# 04-Power-V3P3.net
KiCad netlist of a schematic drawn in Altium Designer
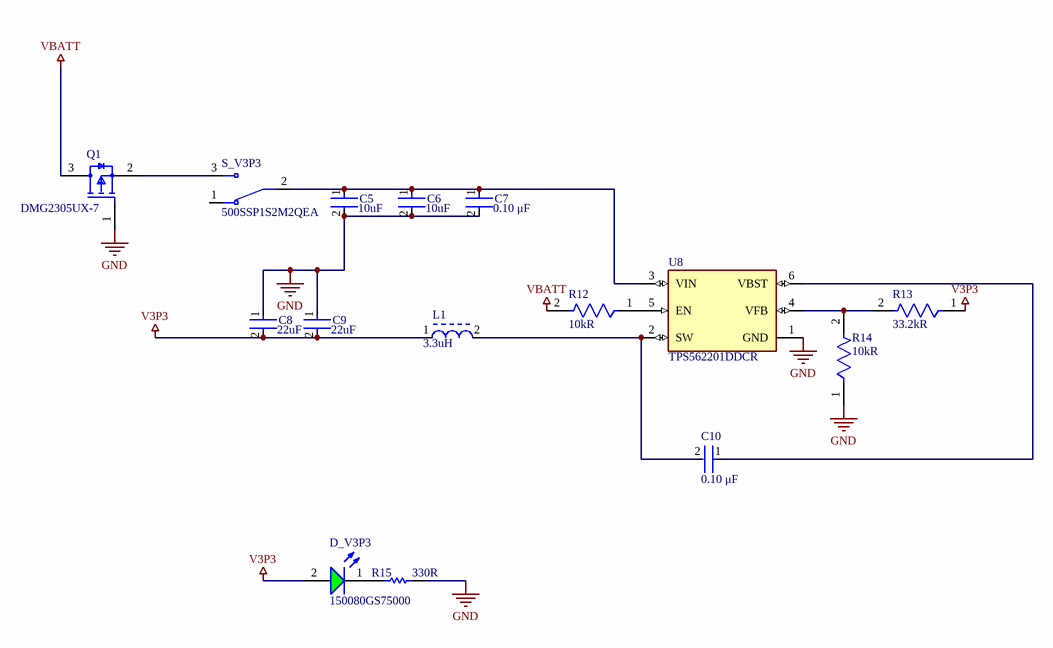
[diagram p0: 04-Power-V3P3.SchDoc]

(export (version "E")
  (design (tool "Eeschema 10.0.6"))
  (components
    (comp (ref "C5")
      (value "GRM21BR61E106KA73L")
      (footprint "FP-GRM21B-0_15-IPC_C")
      (description "Chip Multilayer Ceramic Capacitors for General Purpose, 0805, 10uF, X5R, 15%, 10%, 25V")
      (fields
        (field (name "VOLTAGE") "25V")
        (field (name "CAPACITANCE") "10uF")
        (field (name "TOLERANCE") "10%")
      )
      (libsource (lib "Altium Content Vault") (part "b4654b650e69147ec39a6b967a45e02"))
    )
    (comp (ref "C6")
      (value "GRM21BR61E106KA73L")
      (footprint "FP-GRM21B-0_15-IPC_C")
      (description "Chip Multilayer Ceramic Capacitors for General Purpose, 0805, 10uF, X5R, 15%, 10%, 25V")
      (fields
        (field (name "VOLTAGE") "25V")
        (field (name "CAPACITANCE") "10uF")
        (field (name "TOLERANCE") "10%")
      )
      (libsource (lib "Altium Content Vault") (part "b4654b650e69147ec39a6b967a45e02"))
    )
    (comp (ref "C7")
      (value "0.10 μF")
      (footprint "FP-C0805C-DN-MFG")
      (description "CAP CER 0.1UF 50V X7R 0805")
      (fields
        (field (name "MANUFACTURER PART NUMBER") "C0805C104K5RACTU")
        (field (name "MANUFACTURER") "KEMET")
      )
      (libsource (lib "Altium Content Vault") (part "b4654b650e69147ec39a6b967a45e02"))
    )
    (comp (ref "C8")
      (value "GRM21BR61E226ME44L")
      (footprint "FP-GRM21B-0_2-e0_2_0_7-IPC_B")
      (description "Chip Multilayer Ceramic Capacitors for General Purpose, 0805, 22uF, X5R, 15%, 20%, 25V")
      (fields
        (field (name "TOLERANCE") "20%")
        (field (name "CAPACITANCE") "22uF")
        (field (name "VOLTAGE") "25V")
      )
      (libsource (lib "Altium Content Vault") (part "b4654b650e69147ec39a6b967a45e02"))
    )
    (comp (ref "C9")
      (value "GRM21BR61E226ME44L")
      (footprint "FP-GRM21B-0_2-e0_2_0_7-IPC_B")
      (description "Chip Multilayer Ceramic Capacitors for General Purpose, 0805, 22uF, X5R, 15%, 20%, 25V")
      (fields
        (field (name "TOLERANCE") "20%")
        (field (name "CAPACITANCE") "22uF")
        (field (name "VOLTAGE") "25V")
      )
      (libsource (lib "Altium Content Vault") (part "b4654b650e69147ec39a6b967a45e02"))
    )
    (comp (ref "C10")
      (value "0.10 μF")
      (footprint "FP-C0805C-DN-MFG")
      (description "CAP CER 0.1UF 50V X7R 0805")
      (fields
        (field (name "MANUFACTURER PART NUMBER") "C0805C104K5RACTU")
        (field (name "MANUFACTURER") "KEMET")
      )
      (libsource (lib "Altium Content Vault") (part "b4654b650e69147ec39a6b967a45e02"))
    )
    (comp (ref "D_V3P3")
      (value "150080GS75000")
      (footprint "WL-SMCW_0805_150080xx75000")
      (description "LED GREEN CLEAR 0805 SMD")
      (fields (field (name "MANUFACTURER") "Wurth Electronics"))
      (libsource (lib "Altium Content Vault") (part "LED_Green_2A-1K"))
    )
    (comp (ref "L1")
      (value "SRN6045-3R3Y")
      (footprint "FP-SRN6045-MFG")
      (description "FIXED IND 3.3UH 3.2A 30.2MOHM SM")
      (fields
        (field (name "INDUCTANCE") "3.3uH")
        (field (name "TOLERANCE") "30%")
        (field (name "MANUFACTURER") "Bourns")
      )
      (libsource (lib "Altium Content Vault") (part "e3fba2ffd49a0ea5f20e61e1dfb215d"))
    )
    (comp (ref "Q1")
      (value "DMG2305UX-7")
      (footprint "FP-SOT23-IPC_B")
      (description "MOSFET P-CH 20V 4.2A SOT23")
      (libsource (lib "Altium Content Vault") (part "87831b450059b469d4a68f5364f4496"))
    )
    (comp (ref "R12")
      (value "RMCF0805FT10K0")
      (footprint "FP-RMCF0805-MFG")
      (description "RES 10K OHM 1% 1/8W 0805")
      (fields
        (field (name "TOLERANCE") "1%")
        (field (name "RESISTANCE") "10kR")
        (field (name "MANUFACTURER") "Stackpole Electronics")
      )
      (libsource (lib "Altium Content Vault") (part "1029c3af85768c4190bb7ad29bc67b5"))
    )
    (comp (ref "R13")
      (value "RMCF0805FT33K2")
      (footprint "FP-RMCF0805-IPC_A")
      (description "33.2kΩ ±1% 0.125W 0805 Thick Film Chip Resistor AEC-Q200 compliant")
      (fields
        (field (name "RESISTANCE") "33.2kR")
        (field (name "TOLERANCE") "1%")
        (field (name "MANUFACTURER") "Stackpole Electronics")
      )
      (libsource (lib "Altium Content Vault") (part "1029c3af85768c4190bb7ad29bc67b5"))
    )
    (comp (ref "R14")
      (value "RMCF0805FT10K0")
      (footprint "FP-RMCF0805-MFG")
      (description "RES 10K OHM 1% 1/8W 0805")
      (fields
        (field (name "TOLERANCE") "1%")
        (field (name "RESISTANCE") "10kR")
        (field (name "MANUFACTURER") "Stackpole Electronics")
      )
      (libsource (lib "Altium Content Vault") (part "1029c3af85768c4190bb7ad29bc67b5"))
    )
    (comp (ref "R15")
      (value "330R")
      (footprint "RESC2013X60X40LL20T25")
      (description "RES SMD 330 OHM 1% 1/8W 0805")
      (fields
        (field (name "MANUFACTURER") "Panasonic")
        (field (name "MANUFACTURER PART NUMBER") "ERJ-6ENF3300V")
      )
      (libsource (lib "Altium Content Vault") (part "RES"))
    )
    (comp (ref "S_V3P3")
      (value "500SSP1S2M2QEA")
      (footprint "mjindal2_pcblib:SW_500SSP1S2M2QEA")
      (description "Slide Switch SPDT Through Hole")
      (libsource (lib "mjindal2_schlib") (part "500SSP1S2M2QEA"))
    )
    (comp (ref "U8")
      (value "TPS562201DDCR")
      (footprint "FP-DDC0006A-IPC_C")
      (description "IC REG BUCK ADJ 2A TSOT23-6")
      (libsource (lib "Altium Content Vault") (part "957e164956730ea4bf6293280af19fc"))
    )
  )
  (nets
    (net (code "1") (name "GND") (class "Default")
      (node (ref "C5") (pin "2") (pinfunction "2_2") (pintype "passive"))
      (node (ref "C6") (pin "2") (pinfunction "2_2") (pintype "passive"))
      (node (ref "C7") (pin "2") (pinfunction "2_2") (pintype "passive"))
      (node (ref "C8") (pin "1") (pinfunction "1_1") (pintype "passive"))
      (node (ref "C9") (pin "1") (pinfunction "1_1") (pintype "passive"))
      (node (ref "Q1") (pin "1") (pinfunction "GATE_1") (pintype "passive"))
      (node (ref "R14") (pin "1") (pinfunction "1_1") (pintype "passive"))
      (node (ref "R15") (pin "1") (pinfunction "1_1") (pintype "passive"))
      (node (ref "U8") (pin "1") (pinfunction "GND_1") (pintype "power_in"))
    )
    (net (code "2") (name "Net-(D_V3P3-K)") (class "Default")
      (node (ref "D_V3P3") (pin "1") (pinfunction "K_1") (pintype "passive"))
      (node (ref "R15") (pin "2") (pinfunction "2_2") (pintype "passive"))
    )
    (net (code "3") (name "Net-(Q1-SOURCE)") (class "Default")
      (node (ref "Q1") (pin "2") (pinfunction "SOURCE_2") (pintype "passive"))
      (node (ref "S_V3P3") (pin "3") (pinfunction "NO_3") (pintype "passive"))
    )
    (net (code "4") (name "Net-(S_V3P3-COM)") (class "Default")
      (node (ref "C5") (pin "1") (pinfunction "1_1") (pintype "passive"))
      (node (ref "C6") (pin "1") (pinfunction "1_1") (pintype "passive"))
      (node (ref "C7") (pin "1") (pinfunction "1_1") (pintype "passive"))
      (node (ref "S_V3P3") (pin "2") (pinfunction "COM_2") (pintype "passive"))
      (node (ref "U8") (pin "3") (pinfunction "VIN_3") (pintype "bidirectional"))
    )
    (net (code "5") (name "Net-(U8-EN)") (class "Default")
      (node (ref "R12") (pin "1") (pinfunction "1_1") (pintype "passive"))
      (node (ref "U8") (pin "5") (pinfunction "EN_5") (pintype "input"))
    )
    (net (code "6") (name "Net-(U8-SW)") (class "Default")
      (node (ref "C10") (pin "2") (pinfunction "2_2") (pintype "passive"))
      (node (ref "L1") (pin "2") (pinfunction "2_2") (pintype "passive"))
      (node (ref "U8") (pin "2") (pinfunction "SW_2") (pintype "bidirectional"))
    )
    (net (code "7") (name "Net-(U8-VBST)") (class "Default")
      (node (ref "C10") (pin "1") (pinfunction "1_1") (pintype "passive"))
      (node (ref "U8") (pin "6") (pinfunction "VBST_6") (pintype "bidirectional"))
    )
    (net (code "8") (name "Net-(U8-VFB)") (class "Default")
      (node (ref "R13") (pin "2") (pinfunction "2_2") (pintype "passive"))
      (node (ref "R14") (pin "2") (pinfunction "2_2") (pintype "passive"))
      (node (ref "U8") (pin "4") (pinfunction "VFB_4") (pintype "bidirectional"))
    )
    (net (code "9") (name "V3P3") (class "Default")
      (node (ref "C8") (pin "2") (pinfunction "2_2") (pintype "passive"))
      (node (ref "C9") (pin "2") (pinfunction "2_2") (pintype "passive"))
      (node (ref "D_V3P3") (pin "2") (pinfunction "A_2") (pintype "passive"))
      (node (ref "L1") (pin "1") (pinfunction "1_1") (pintype "passive"))
      (node (ref "R13") (pin "1") (pinfunction "1_1") (pintype "passive"))
    )
    (net (code "10") (name "VBATT") (class "Default")
      (node (ref "Q1") (pin "3") (pinfunction "DRAIN_3") (pintype "passive"))
      (node (ref "R12") (pin "2") (pinfunction "2_2") (pintype "passive"))
    )
    (net (code "11") (name "unconnected-(S_V3P3-NC-Pad1)") (class "Default")
      (node (ref "S_V3P3") (pin "1") (pinfunction "NC_1") (pintype "passive"))
    )
  )
)
